# balancer_winston-odpor.net
KiCad netlist of a schematic drawn in EAGLE
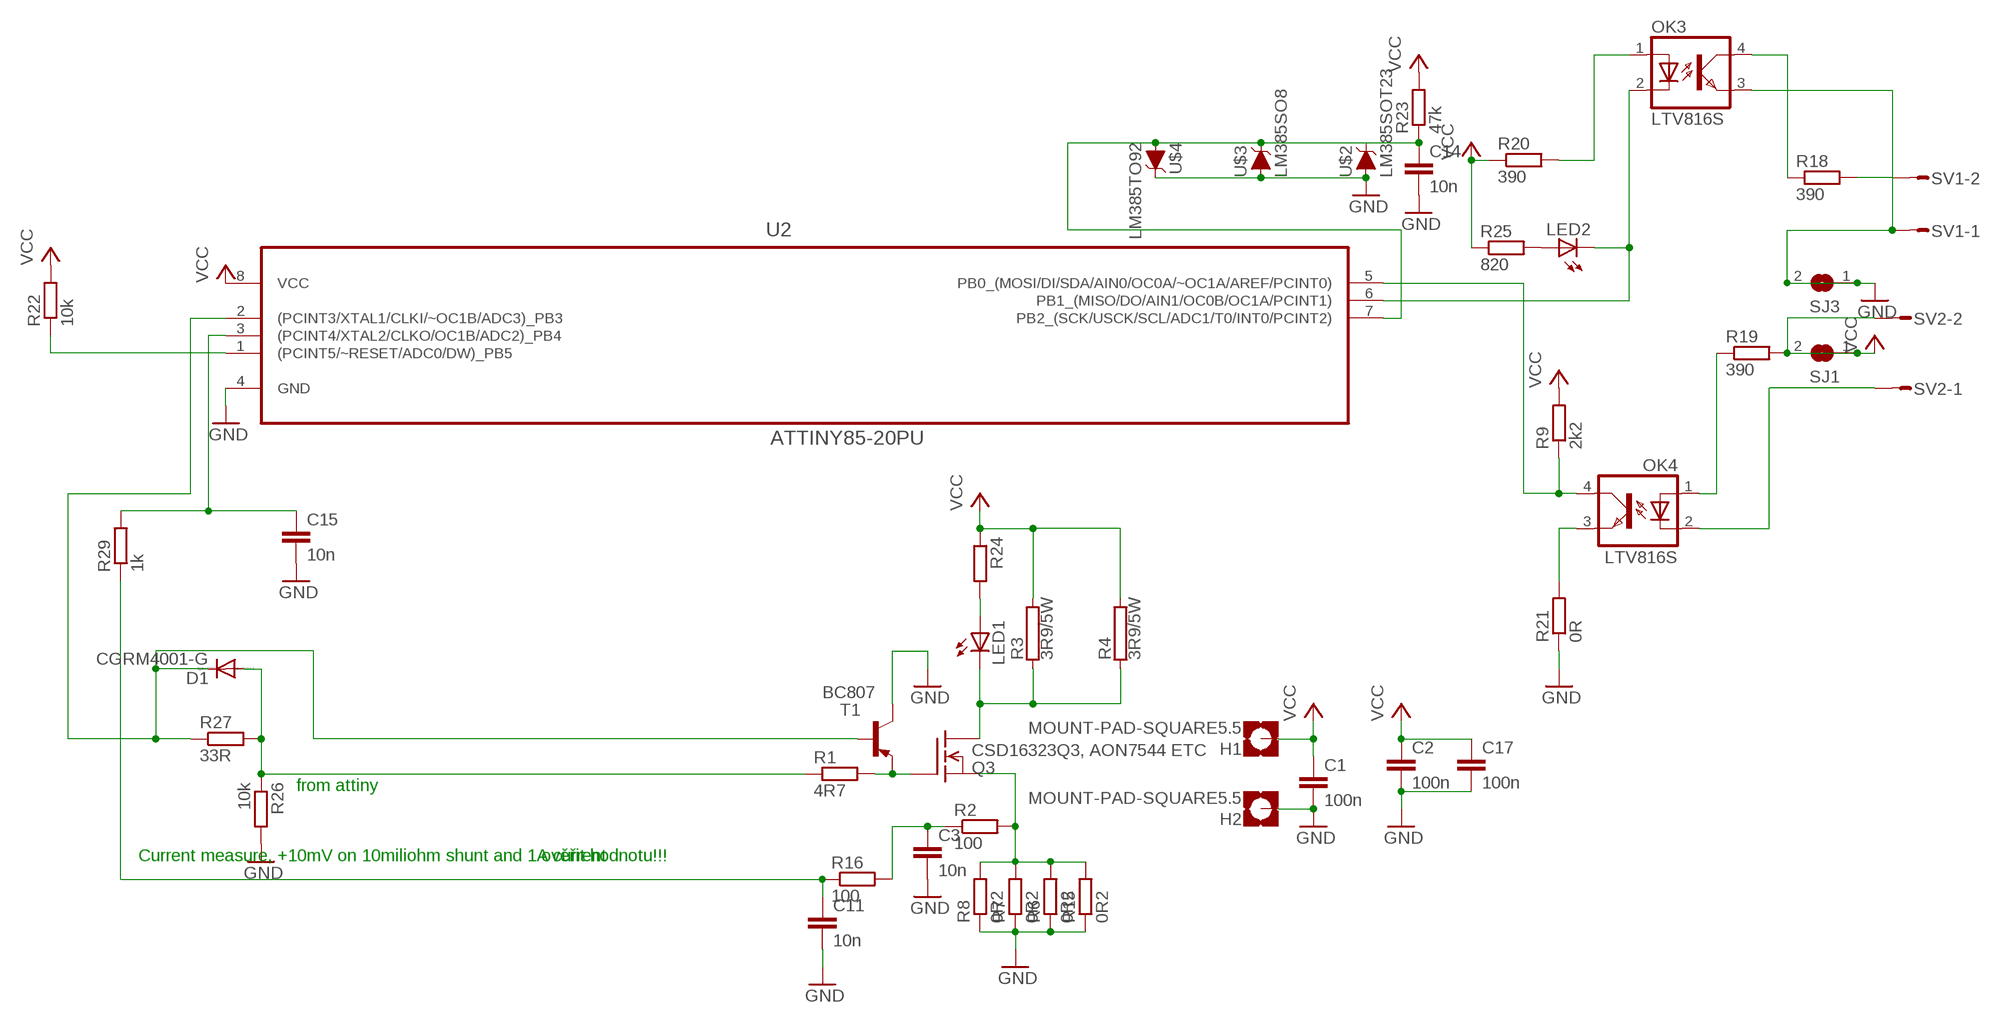
[diagram p0: schematic, sheet 1]

(export (version "E")
  (design (tool "Eeschema 10.0.6"))
  (components
    (comp (ref "C1")
      (value "100n")
      (footprint "eagle-import:C1210K")
      (libsource (lib "eagle-import") (part "C-EUC1210K"))
    )
    (comp (ref "C2")
      (value "100n")
      (footprint "eagle-import:C1210K")
      (libsource (lib "eagle-import") (part "C-EUC1210K"))
    )
    (comp (ref "C3")
      (value "10n")
      (footprint "eagle-import:C0603")
      (libsource (lib "eagle-import") (part "C-EUC0603"))
    )
    (comp (ref "C11")
      (value "10n")
      (footprint "eagle-import:C0603")
      (libsource (lib "eagle-import") (part "C-EUC0603"))
    )
    (comp (ref "C14")
      (value "10n")
      (footprint "eagle-import:C0603")
      (libsource (lib "eagle-import") (part "C-EUC0603"))
    )
    (comp (ref "C15")
      (value "10n")
      (footprint "eagle-import:C0603")
      (libsource (lib "eagle-import") (part "C-EUC0603"))
    )
    (comp (ref "C17")
      (value "100n")
      (footprint "eagle-import:C1210K")
      (libsource (lib "eagle-import") (part "C-EUC1210K"))
    )
    (comp (ref "D1")
      (value "CGRM4001-G")
      (footprint "eagle-import:SOD-123_MINI-SMA")
      (libsource (lib "eagle-import") (part "CGRM400-G1"))
    )
    (comp (ref "H1")
      (value "MOUNT-PAD-SQUARE5.5")
      (footprint "eagle-import:5,5-PAD-SQUARE")
      (libsource (lib "eagle-import") (part "MOUNT-PAD-SQUARE5.5"))
    )
    (comp (ref "H2")
      (value "MOUNT-PAD-SQUARE5.5")
      (footprint "eagle-import:5,5-PAD-SQUARE")
      (libsource (lib "eagle-import") (part "MOUNT-PAD-SQUARE5.5"))
    )
    (comp (ref "LED1")
      (value "LED3MM")
      (footprint "eagle-import:LED3MM")
      (libsource (lib "eagle-import") (part "LED3MM"))
    )
    (comp (ref "LED2")
      (value "LED3MM")
      (footprint "eagle-import:LED3MM")
      (libsource (lib "eagle-import") (part "LED3MM"))
    )
    (comp (ref "OK3")
      (value "LTV816S")
      (footprint "eagle-import:SMD4")
      (libsource (lib "eagle-import") (part "LTV816S"))
    )
    (comp (ref "OK4")
      (value "LTV816S")
      (footprint "eagle-import:SMD4")
      (libsource (lib "eagle-import") (part "LTV816S"))
    )
    (comp (ref "Q3")
      (value "CSD16323Q3, AON7544 ETC")
      (footprint "eagle-import:SON33X33")
      (libsource (lib "eagle-import") (part "CSD16323Q3"))
    )
    (comp (ref "R1")
      (value "4R7")
      (footprint "eagle-import:R0603")
      (libsource (lib "eagle-import") (part "R-EU_R0603"))
    )
    (comp (ref "R2")
      (value "100")
      (footprint "eagle-import:R0603")
      (libsource (lib "eagle-import") (part "R-EU_R0603"))
    )
    (comp (ref "R3")
      (value "3R9/5W")
      (footprint "eagle-import:HPS932")
      (libsource (lib "eagle-import") (part "RHPS932"))
    )
    (comp (ref "R4")
      (value "3R9/5W")
      (footprint "eagle-import:HPS932")
      (libsource (lib "eagle-import") (part "RHPS932"))
    )
    (comp (ref "R6")
      (value "0R2")
      (footprint "eagle-import:M1206")
      (libsource (lib "eagle-import") (part "R-EU_M1206"))
    )
    (comp (ref "R7")
      (value "0R2")
      (footprint "eagle-import:M1206")
      (libsource (lib "eagle-import") (part "R-EU_M1206"))
    )
    (comp (ref "R8")
      (value "0R2")
      (footprint "eagle-import:M1206")
      (libsource (lib "eagle-import") (part "R-EU_M1206"))
    )
    (comp (ref "R9")
      (value "2k2")
      (footprint "eagle-import:R0603")
      (libsource (lib "eagle-import") (part "R-EU_R0603"))
    )
    (comp (ref "R15")
      (value "0R2")
      (footprint "eagle-import:M1206")
      (libsource (lib "eagle-import") (part "R-EU_M1206"))
    )
    (comp (ref "R16")
      (value "100")
      (footprint "eagle-import:R0603")
      (libsource (lib "eagle-import") (part "R-EU_R0603"))
    )
    (comp (ref "R18")
      (value "390")
      (footprint "eagle-import:R0603")
      (libsource (lib "eagle-import") (part "R-EU_R0603"))
    )
    (comp (ref "R19")
      (value "390")
      (footprint "eagle-import:R0603")
      (libsource (lib "eagle-import") (part "R-EU_R0603"))
    )
    (comp (ref "R20")
      (value "390")
      (footprint "eagle-import:R0603")
      (libsource (lib "eagle-import") (part "R-EU_R0603"))
    )
    (comp (ref "R21")
      (value "0R")
      (footprint "eagle-import:R0603")
      (libsource (lib "eagle-import") (part "R-EU_R0603"))
    )
    (comp (ref "R22")
      (value "10k")
      (footprint "eagle-import:R0805")
      (libsource (lib "eagle-import") (part "R-EU_R0805"))
    )
    (comp (ref "R23")
      (value "47k")
      (footprint "eagle-import:R0603")
      (libsource (lib "eagle-import") (part "R-EU_R0603"))
    )
    (comp (ref "R24")
      (value "R-EU_R0603")
      (footprint "eagle-import:R0603")
      (libsource (lib "eagle-import") (part "R-EU_R0603"))
    )
    (comp (ref "R25")
      (value "820")
      (footprint "eagle-import:R0805")
      (libsource (lib "eagle-import") (part "R-EU_R0805"))
    )
    (comp (ref "R26")
      (value "10k")
      (footprint "eagle-import:R0603")
      (libsource (lib "eagle-import") (part "R-EU_R0603"))
    )
    (comp (ref "R27")
      (value "33R")
      (footprint "eagle-import:R0603")
      (libsource (lib "eagle-import") (part "R-EU_R0603"))
    )
    (comp (ref "R29")
      (value "1k")
      (footprint "eagle-import:R0603")
      (libsource (lib "eagle-import") (part "R-EU_R0603"))
    )
    (comp (ref "SJ1") (value "SJ") (footprint "eagle-import:SJ") (libsource (lib "eagle-import") (part "SJ")))
    (comp (ref "SJ3") (value "SJ") (footprint "eagle-import:SJ") (libsource (lib "eagle-import") (part "SJ")))
    (comp (ref "SV1")
      (value "S02P")
      (footprint "eagle-import:S02P")
      (libsource (lib "eagle-import") (part "S02P"))
    )
    (comp (ref "SV2")
      (value "S02P")
      (footprint "eagle-import:S02P")
      (libsource (lib "eagle-import") (part "S02P"))
    )
    (comp (ref "T1")
      (value "BC807")
      (footprint "eagle-import:SOT23-BEC")
      (libsource (lib "eagle-import") (part "-PNP-SOT23-BECBC807-16LT1"))
    )
    (comp (ref "U$2")
      (value "LM385SOT23")
      (footprint "eagle-import:SOT23-3")
      (libsource (lib "eagle-import") (part "LM385SOT23"))
    )
    (comp (ref "U$3")
      (value "LM385SO8")
      (footprint "eagle-import:SO08")
      (libsource (lib "eagle-import") (part "LM385SO8"))
    )
    (comp (ref "U$4")
      (value "LM385TO92")
      (footprint "eagle-import:TO-92")
      (libsource (lib "eagle-import") (part "LM385TO92"))
    )
    (comp (ref "U2")
      (value "ATTINY85-20PU")
      (footprint "eagle-import:DIP254P762X533-8")
      (libsource (lib "eagle-import") (part "ATTINY85-20PU"))
    )
  )
  (nets
    (net (code "1") (name "GND") (class "Default")
      (node (ref "C1") (pin "2") (pinfunction "2_2") (pintype "passive"))
      (node (ref "C11") (pin "2") (pinfunction "2_2") (pintype "passive"))
      (node (ref "C14") (pin "2") (pinfunction "2_2") (pintype "passive"))
      (node (ref "C15") (pin "2") (pinfunction "2_2") (pintype "passive"))
      (node (ref "C17") (pin "2") (pinfunction "2_2") (pintype "passive"))
      (node (ref "C2") (pin "2") (pinfunction "2_2") (pintype "passive"))
      (node (ref "C3") (pin "2") (pinfunction "2_2") (pintype "passive"))
      (node (ref "H2") (pin "B5,5") (pinfunction "MOUNT_B5,5") (pintype "passive"))
      (node (ref "OK3") (pin "3") (pinfunction "EMIT_3") (pintype "passive"))
      (node (ref "R15") (pin "1") (pinfunction "1_1") (pintype "passive"))
      (node (ref "R21") (pin "1") (pinfunction "1_1") (pintype "passive"))
      (node (ref "R26") (pin "2") (pinfunction "2_2") (pintype "passive"))
      (node (ref "R6") (pin "1") (pinfunction "1_1") (pintype "passive"))
      (node (ref "R7") (pin "1") (pinfunction "1_1") (pintype "passive"))
      (node (ref "R8") (pin "1") (pinfunction "1_1") (pintype "passive"))
      (node (ref "SJ3") (pin "1") (pinfunction "1_1") (pintype "passive"))
      (node (ref "SJ3") (pin "2") (pinfunction "2_2") (pintype "passive"))
      (node (ref "SV1") (pin "1") (pinfunction "S_1") (pintype "passive"))
      (node (ref "T1") (pin "C") (pinfunction "C_C") (pintype "passive"))
      (node (ref "U$2") (pin "1") (pinfunction "A_1") (pintype "passive"))
      (node (ref "U$3") (pin "8") (pinfunction "A_8") (pintype "passive"))
      (node (ref "U$4") (pin "3") (pinfunction "C_3") (pintype "passive"))
      (node (ref "U2") (pin "4") (pinfunction "GND_4") (pintype "passive"))
    )
    (net (code "2") (name "Net-(C3-Pad1)") (class "Default")
      (node (ref "C3") (pin "1") (pinfunction "1_1") (pintype "passive"))
      (node (ref "R16") (pin "2") (pinfunction "2_2") (pintype "passive"))
      (node (ref "R2") (pin "1") (pinfunction "1_1") (pintype "passive"))
    )
    (net (code "3") (name "Net-(C11-Pad1)") (class "Default")
      (node (ref "C11") (pin "1") (pinfunction "1_1") (pintype "passive"))
      (node (ref "R16") (pin "1") (pinfunction "1_1") (pintype "passive"))
      (node (ref "R29") (pin "1") (pinfunction "1_1") (pintype "passive"))
    )
    (net (code "4") (name "Net-(D1-PadA)") (class "Default")
      (node (ref "D1") (pin "A") (pinfunction "A_A") (pintype "passive"))
      (node (ref "R1") (pin "1") (pinfunction "1_1") (pintype "passive"))
      (node (ref "R26") (pin "1") (pinfunction "1_1") (pintype "passive"))
      (node (ref "R27") (pin "2") (pinfunction "2_2") (pintype "passive"))
    )
    (net (code "5") (name "Net-(LED1-C)") (class "Default")
      (node (ref "LED1") (pin "K") (pinfunction "C_K") (pintype "passive"))
      (node (ref "Q3") (pin "EXP") (pinfunction "D_EXP") (pintype "passive"))
      (node (ref "R3") (pin "1") (pinfunction "1_1") (pintype "passive"))
      (node (ref "R4") (pin "1") (pinfunction "1_1") (pintype "passive"))
    )
    (net (code "6") (name "Net-(LED1-PadA)") (class "Default")
      (node (ref "LED1") (pin "A") (pinfunction "A_A") (pintype "passive"))
      (node (ref "R24") (pin "2") (pinfunction "2_2") (pintype "passive"))
    )
    (net (code "7") (name "Net-(LED2-C)") (class "Default")
      (node (ref "LED2") (pin "K") (pinfunction "C_K") (pintype "passive"))
      (node (ref "OK3") (pin "2") (pinfunction "C_2") (pintype "passive"))
      (node (ref "U2") (pin "6") (pinfunction "PB1_(MISO/DO/AIN1/OC0B/OC1A/PCINT1)_6") (pintype "bidirectional"))
    )
    (net (code "8") (name "Net-(LED2-PadA)") (class "Default")
      (node (ref "LED2") (pin "A") (pinfunction "A_A") (pintype "passive"))
      (node (ref "R25") (pin "2") (pinfunction "2_2") (pintype "passive"))
    )
    (net (code "9") (name "Net-(OK3-A)") (class "Default")
      (node (ref "OK3") (pin "1") (pinfunction "A_1") (pintype "passive"))
      (node (ref "R20") (pin "2") (pinfunction "2_2") (pintype "passive"))
    )
    (net (code "10") (name "Net-(OK3-COL)") (class "Default")
      (node (ref "OK3") (pin "4") (pinfunction "COL_4") (pintype "passive"))
      (node (ref "R18") (pin "1") (pinfunction "1_1") (pintype "passive"))
    )
    (net (code "11") (name "Net-(OK4-A)") (class "Default")
      (node (ref "OK4") (pin "1") (pinfunction "A_1") (pintype "passive"))
      (node (ref "R19") (pin "1") (pinfunction "1_1") (pintype "passive"))
    )
    (net (code "12") (name "Net-(OK4-C)") (class "Default")
      (node (ref "OK4") (pin "2") (pinfunction "C_2") (pintype "passive"))
      (node (ref "SV2") (pin "1") (pinfunction "S_1") (pintype "passive"))
    )
    (net (code "13") (name "Net-(OK4-COL)") (class "Default")
      (node (ref "OK4") (pin "4") (pinfunction "COL_4") (pintype "passive"))
      (node (ref "R9") (pin "1") (pinfunction "1_1") (pintype "passive"))
      (node (ref "U2") (pin "5") (pinfunction "PB0_(MOSI/DI/SDA/AIN0/OC0A/~{OC1A/AREF/PCINT0})_5") (pintype "bidirectional"))
    )
    (net (code "14") (name "Net-(OK4-EMIT)") (class "Default")
      (node (ref "OK4") (pin "3") (pinfunction "EMIT_3") (pintype "passive"))
      (node (ref "R21") (pin "2") (pinfunction "2_2") (pintype "passive"))
    )
    (net (code "15") (name "Net-(Q3-G)") (class "Default")
      (node (ref "Q3") (pin "4") (pinfunction "G_4") (pintype "passive"))
      (node (ref "R1") (pin "2") (pinfunction "2_2") (pintype "passive"))
      (node (ref "T1") (pin "E") (pinfunction "E_E") (pintype "passive"))
    )
    (net (code "16") (name "Net-(Q3-S-Pad1)") (class "Default")
      (node (ref "Q3") (pin "1") (pinfunction "S_1") (pintype "passive"))
      (node (ref "Q3") (pin "2") (pinfunction "S_2") (pintype "passive"))
      (node (ref "Q3") (pin "3") (pinfunction "S_3") (pintype "passive"))
      (node (ref "R15") (pin "2") (pinfunction "2_2") (pintype "passive"))
      (node (ref "R2") (pin "2") (pinfunction "2_2") (pintype "passive"))
      (node (ref "R6") (pin "2") (pinfunction "2_2") (pintype "passive"))
      (node (ref "R7") (pin "2") (pinfunction "2_2") (pintype "passive"))
      (node (ref "R8") (pin "2") (pinfunction "2_2") (pintype "passive"))
    )
    (net (code "17") (name "Net-(SV1B-S)") (class "Default")
      (node (ref "R18") (pin "2") (pinfunction "2_2") (pintype "passive"))
      (node (ref "SV1") (pin "2") (pinfunction "S_2") (pintype "passive"))
    )
    (net (code "18") (name "Net-(U$2-C)") (class "Default")
      (node (ref "C14") (pin "1") (pinfunction "1_1") (pintype "passive"))
      (node (ref "R23") (pin "1") (pinfunction "1_1") (pintype "passive"))
      (node (ref "U$2") (pin "2") (pinfunction "C_2") (pintype "passive"))
      (node (ref "U$3") (pin "4") (pinfunction "C_4") (pintype "passive"))
      (node (ref "U$4") (pin "2") (pinfunction "A_2") (pintype "passive"))
      (node (ref "U2") (pin "7") (pinfunction "PB2_(SCK/USCK/SCL/ADC1/T0/INT0/PCINT2)_7") (pintype "bidirectional"))
    )
    (net (code "19") (name "Net-(U2-(PCINT3{slash}XTAL1{slash}CLKI{slash}~{OC1B{slash}ADC3})_PB3)") (class "Default")
      (node (ref "D1") (pin "C") (pinfunction "C_C") (pintype "passive"))
      (node (ref "R27") (pin "1") (pinfunction "1_1") (pintype "passive"))
      (node (ref "T1") (pin "B") (pinfunction "B_B") (pintype "passive"))
      (node (ref "U2") (pin "2") (pinfunction "(PCINT3/XTAL1/CLKI/~{OC1B/ADC3})_PB3_2") (pintype "bidirectional"))
    )
    (net (code "20") (name "Net-(U2-(PCINT4{slash}XTAL2{slash}CLKO{slash}OC1B{slash}ADC2)_PB4)") (class "Default")
      (node (ref "C15") (pin "1") (pinfunction "1_1") (pintype "passive"))
      (node (ref "R29") (pin "2") (pinfunction "2_2") (pintype "passive"))
      (node (ref "U2") (pin "3") (pinfunction "(PCINT4/XTAL2/CLKO/OC1B/ADC2)_PB4_3") (pintype "bidirectional"))
    )
    (net (code "21") (name "Net-(U2-(PCINT5{slash}~{RESET{slash}ADC0{slash}DW})_PB5)") (class "Default")
      (node (ref "R22") (pin "1") (pinfunction "1_1") (pintype "passive"))
      (node (ref "U2") (pin "1") (pinfunction "(PCINT5/~{RESET/ADC0/DW})_PB5_1") (pintype "bidirectional"))
    )
    (net (code "22") (name "VCC") (class "Default")
      (node (ref "C1") (pin "1") (pinfunction "1_1") (pintype "passive"))
      (node (ref "C17") (pin "1") (pinfunction "1_1") (pintype "passive"))
      (node (ref "C2") (pin "1") (pinfunction "1_1") (pintype "passive"))
      (node (ref "H1") (pin "B5,5") (pinfunction "MOUNT_B5,5") (pintype "passive"))
      (node (ref "R19") (pin "2") (pinfunction "2_2") (pintype "passive"))
      (node (ref "R20") (pin "1") (pinfunction "1_1") (pintype "passive"))
      (node (ref "R22") (pin "2") (pinfunction "2_2") (pintype "passive"))
      (node (ref "R23") (pin "2") (pinfunction "2_2") (pintype "passive"))
      (node (ref "R24") (pin "1") (pinfunction "1_1") (pintype "passive"))
      (node (ref "R25") (pin "1") (pinfunction "1_1") (pintype "passive"))
      (node (ref "R3") (pin "2") (pinfunction "2_2") (pintype "passive"))
      (node (ref "R4") (pin "2") (pinfunction "2_2") (pintype "passive"))
      (node (ref "R9") (pin "2") (pinfunction "2_2") (pintype "passive"))
      (node (ref "SJ1") (pin "1") (pinfunction "1_1") (pintype "passive"))
      (node (ref "SJ1") (pin "2") (pinfunction "2_2") (pintype "passive"))
      (node (ref "SV2") (pin "2") (pinfunction "S_2") (pintype "passive"))
      (node (ref "U2") (pin "8") (pinfunction "VCC_8") (pintype "power_in"))
    )
  )
)
